# schematics.net
KiCad netlist of a schematic drawn in EAGLE
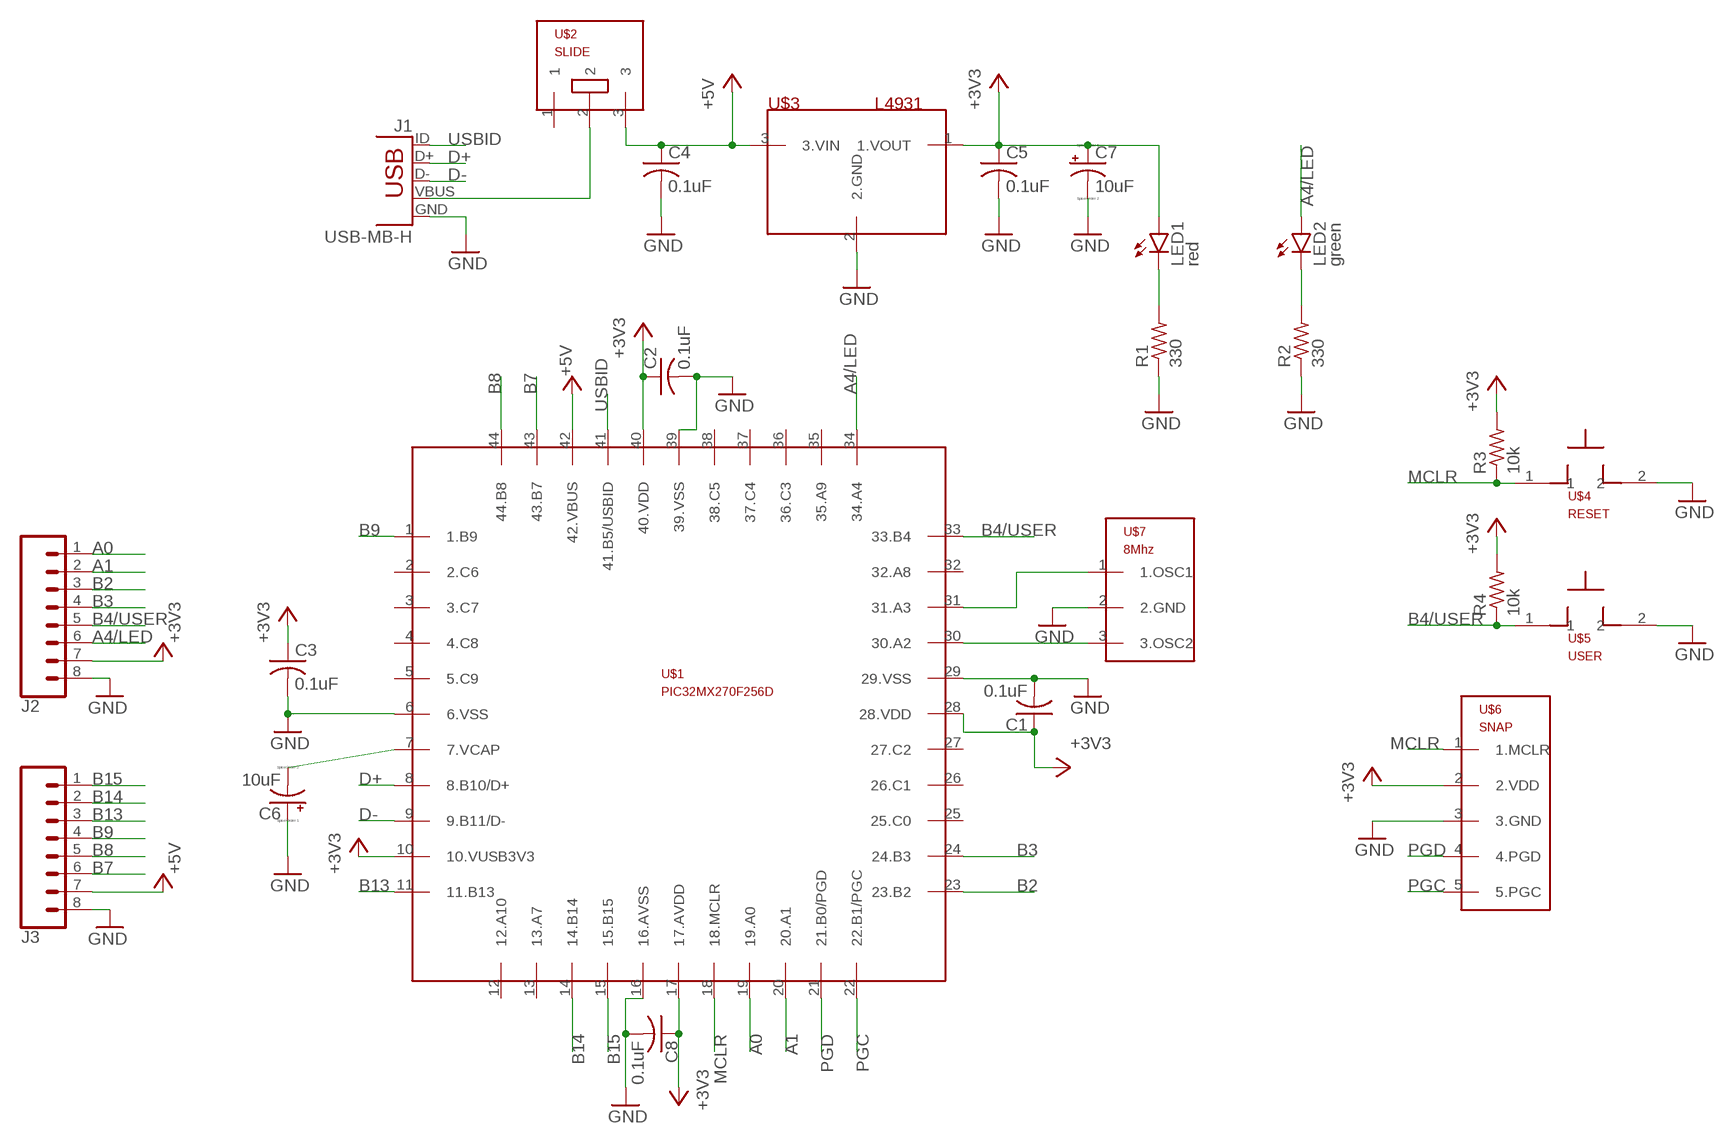
[diagram p0: schematic, sheet 1]

(export (version "E")
  (design (tool "Eeschema 10.0.6"))
  (components
    (comp (ref "C1")
      (value "0.1uF")
      (footprint "eagle-import:C025-025X050")
      (libsource (lib "eagle-import") (part "C-US025-025X050"))
    )
    (comp (ref "C2")
      (value "0.1uF")
      (footprint "eagle-import:C025-025X050")
      (libsource (lib "eagle-import") (part "C-US025-025X050"))
    )
    (comp (ref "C3")
      (value "0.1uF")
      (footprint "eagle-import:C025-025X050")
      (libsource (lib "eagle-import") (part "C-US025-025X050"))
    )
    (comp (ref "C4")
      (value "0.1uF")
      (footprint "eagle-import:C025-025X050")
      (libsource (lib "eagle-import") (part "C-US025-025X050"))
    )
    (comp (ref "C5")
      (value "0.1uF")
      (footprint "eagle-import:C025-025X050")
      (libsource (lib "eagle-import") (part "C-US025-025X050"))
    )
    (comp (ref "C6")
      (value "10uF")
      (footprint "eagle-import:B45181B")
      (libsource (lib "eagle-import") (part "CPOL-USB45181B"))
    )
    (comp (ref "C7")
      (value "10uF")
      (footprint "eagle-import:B45181B")
      (libsource (lib "eagle-import") (part "CPOL-USB45181B"))
    )
    (comp (ref "C8")
      (value "0.1uF")
      (footprint "eagle-import:C025-025X050")
      (libsource (lib "eagle-import") (part "C-US025-025X050"))
    )
    (comp (ref "J1")
      (value "USB-MB-H")
      (footprint "eagle-import:USB-MB-H")
      (libsource (lib "eagle-import") (part "USB-MB-H"))
    )
    (comp (ref "J2")
      (value "CONN_08\"")
      (footprint "eagle-import:1X08")
      (libsource (lib "eagle-import") (part "CONN_08{dblquote}"))
    )
    (comp (ref "J3")
      (value "CONN_08\"")
      (footprint "eagle-import:1X08")
      (libsource (lib "eagle-import") (part "CONN_08{dblquote}"))
    )
    (comp (ref "LED1")
      (value "red")
      (footprint "eagle-import:LED3MM")
      (libsource (lib "eagle-import") (part "LED3MM"))
    )
    (comp (ref "LED2")
      (value "green")
      (footprint "eagle-import:LED3MM")
      (libsource (lib "eagle-import") (part "LED3MM"))
    )
    (comp (ref "R1")
      (value "330")
      (footprint "eagle-import:0207_10")
      (libsource (lib "eagle-import") (part "R-US_0207/10"))
    )
    (comp (ref "R2")
      (value "330")
      (footprint "eagle-import:0207_10")
      (libsource (lib "eagle-import") (part "R-US_0207/10"))
    )
    (comp (ref "R3")
      (value "10k")
      (footprint "eagle-import:0207_10")
      (libsource (lib "eagle-import") (part "R-US_0207/10"))
    )
    (comp (ref "R4")
      (value "10k")
      (footprint "eagle-import:0207_10")
      (libsource (lib "eagle-import") (part "R-US_0207/10"))
    )
    (comp (ref "U$1")
      (value "PIC32MX270F256D")
      (footprint "eagle-import:TQFP44")
      (libsource (lib "eagle-import") (part "PIC32MX270F256D"))
    )
    (comp (ref "U$2")
      (value "SLIDE")
      (footprint "eagle-import:SLIDE")
      (libsource (lib "eagle-import") (part "SLIDE"))
    )
    (comp (ref "U$3")
      (value "L4931")
      (footprint "eagle-import:TO92")
      (libsource (lib "eagle-import") (part "L4931"))
    )
    (comp (ref "U$4")
      (value "RESET")
      (footprint "eagle-import:PB")
      (libsource (lib "eagle-import") (part "PB"))
    )
    (comp (ref "U$5")
      (value "USER")
      (footprint "eagle-import:PB")
      (libsource (lib "eagle-import") (part "PB"))
    )
    (comp (ref "U$6")
      (value "SNAP")
      (footprint "eagle-import:SNAP")
      (libsource (lib "eagle-import") (part "SNAP"))
    )
    (comp (ref "U$7")
      (value "8Mhz")
      (footprint "eagle-import:OSC")
      (libsource (lib "eagle-import") (part "OSC"))
    )
  )
  (nets
    (net (code "1") (name "+3V3") (class "Default")
      (node (ref "C1") (pin "1") (pinfunction "1_1") (pintype "passive"))
      (node (ref "C2") (pin "1") (pinfunction "1_1") (pintype "passive"))
      (node (ref "C3") (pin "1") (pinfunction "1_1") (pintype "passive"))
      (node (ref "C5") (pin "1") (pinfunction "1_1") (pintype "passive"))
      (node (ref "C7") (pin "+") (pinfunction "+_+") (pintype "passive"))
      (node (ref "C8") (pin "1") (pinfunction "1_1") (pintype "passive"))
      (node (ref "J2") (pin "7") (pinfunction "7_7") (pintype "passive"))
      (node (ref "LED1") (pin "A") (pinfunction "A_A") (pintype "passive"))
      (node (ref "R3") (pin "2") (pinfunction "2_2") (pintype "passive"))
      (node (ref "R4") (pin "2") (pinfunction "2_2") (pintype "passive"))
      (node (ref "U$1") (pin "10") (pinfunction "10.VUSB3V3_10") (pintype "bidirectional"))
      (node (ref "U$1") (pin "17") (pinfunction "17.AVDD_17") (pintype "bidirectional"))
      (node (ref "U$1") (pin "28") (pinfunction "28.VDD_28") (pintype "bidirectional"))
      (node (ref "U$1") (pin "40") (pinfunction "40.VDD_40") (pintype "bidirectional"))
      (node (ref "U$3") (pin "1") (pinfunction "1.VOUT_1") (pintype "bidirectional"))
      (node (ref "U$6") (pin "2") (pinfunction "2.VDD_2") (pintype "bidirectional"))
    )
    (net (code "2") (name "+5V") (class "Default")
      (node (ref "C4") (pin "1") (pinfunction "1_1") (pintype "passive"))
      (node (ref "J3") (pin "7") (pinfunction "7_7") (pintype "passive"))
      (node (ref "U$1") (pin "42") (pinfunction "42.VBUS_42") (pintype "bidirectional"))
      (node (ref "U$2") (pin "3") (pinfunction "3_3") (pintype "bidirectional"))
      (node (ref "U$3") (pin "3") (pinfunction "3.VIN_3") (pintype "bidirectional"))
    )
    (net (code "3") (name "/A0") (class "Default")
      (node (ref "J2") (pin "1") (pinfunction "1_1") (pintype "passive"))
      (node (ref "U$1") (pin "19") (pinfunction "19.A0_19") (pintype "bidirectional"))
    )
    (net (code "4") (name "/A1") (class "Default")
      (node (ref "J2") (pin "2") (pinfunction "2_2") (pintype "passive"))
      (node (ref "U$1") (pin "20") (pinfunction "20.A1_20") (pintype "bidirectional"))
    )
    (net (code "5") (name "/A4{slash}LED") (class "Default")
      (node (ref "J2") (pin "6") (pinfunction "6_6") (pintype "passive"))
      (node (ref "LED2") (pin "A") (pinfunction "A_A") (pintype "passive"))
      (node (ref "U$1") (pin "34") (pinfunction "34.A4_34") (pintype "bidirectional"))
    )
    (net (code "6") (name "/B2") (class "Default")
      (node (ref "J2") (pin "3") (pinfunction "3_3") (pintype "passive"))
      (node (ref "U$1") (pin "23") (pinfunction "23.B2_23") (pintype "bidirectional"))
    )
    (net (code "7") (name "/B3") (class "Default")
      (node (ref "J2") (pin "4") (pinfunction "4_4") (pintype "passive"))
      (node (ref "U$1") (pin "24") (pinfunction "24.B3_24") (pintype "bidirectional"))
    )
    (net (code "8") (name "/B4{slash}USER") (class "Default")
      (node (ref "J2") (pin "5") (pinfunction "5_5") (pintype "passive"))
      (node (ref "R4") (pin "1") (pinfunction "1_1") (pintype "passive"))
      (node (ref "U$1") (pin "33") (pinfunction "33.B4_33") (pintype "bidirectional"))
      (node (ref "U$5") (pin "1") (pinfunction "1_1") (pintype "bidirectional"))
    )
    (net (code "9") (name "/B7") (class "Default")
      (node (ref "J3") (pin "6") (pinfunction "6_6") (pintype "passive"))
      (node (ref "U$1") (pin "43") (pinfunction "43.B7_43") (pintype "bidirectional"))
    )
    (net (code "10") (name "/B8") (class "Default")
      (node (ref "J3") (pin "5") (pinfunction "5_5") (pintype "passive"))
      (node (ref "U$1") (pin "44") (pinfunction "44.B8_44") (pintype "bidirectional"))
    )
    (net (code "11") (name "/B9") (class "Default")
      (node (ref "J3") (pin "4") (pinfunction "4_4") (pintype "passive"))
      (node (ref "U$1") (pin "1") (pinfunction "1.B9_1") (pintype "bidirectional"))
    )
    (net (code "12") (name "/B13") (class "Default")
      (node (ref "J3") (pin "3") (pinfunction "3_3") (pintype "passive"))
      (node (ref "U$1") (pin "11") (pinfunction "11.B13_11") (pintype "bidirectional"))
    )
    (net (code "13") (name "/B14") (class "Default")
      (node (ref "J3") (pin "2") (pinfunction "2_2") (pintype "passive"))
      (node (ref "U$1") (pin "14") (pinfunction "14.B14_14") (pintype "bidirectional"))
    )
    (net (code "14") (name "/B15") (class "Default")
      (node (ref "J3") (pin "1") (pinfunction "1_1") (pintype "passive"))
      (node (ref "U$1") (pin "15") (pinfunction "15.B15_15") (pintype "bidirectional"))
    )
    (net (code "15") (name "/D+") (class "Default")
      (node (ref "J1") (pin "D+") (pinfunction "D+_D+") (pintype "bidirectional"))
      (node (ref "U$1") (pin "8") (pinfunction "8.B10/D+_8") (pintype "bidirectional"))
    )
    (net (code "16") (name "/D-") (class "Default")
      (node (ref "J1") (pin "D-") (pinfunction "D-_D-") (pintype "bidirectional"))
      (node (ref "U$1") (pin "9") (pinfunction "9.B11/D-_9") (pintype "bidirectional"))
    )
    (net (code "17") (name "/MCLR") (class "Default")
      (node (ref "R3") (pin "1") (pinfunction "1_1") (pintype "passive"))
      (node (ref "U$1") (pin "18") (pinfunction "18.MCLR_18") (pintype "bidirectional"))
      (node (ref "U$4") (pin "1") (pinfunction "1_1") (pintype "bidirectional"))
      (node (ref "U$6") (pin "1") (pinfunction "1.MCLR_1") (pintype "bidirectional"))
    )
    (net (code "18") (name "/PGC") (class "Default")
      (node (ref "U$1") (pin "22") (pinfunction "22.B1/PGC_22") (pintype "bidirectional"))
      (node (ref "U$6") (pin "5") (pinfunction "5.PGC_5") (pintype "bidirectional"))
    )
    (net (code "19") (name "/PGD") (class "Default")
      (node (ref "U$1") (pin "21") (pinfunction "21.B0/PGD_21") (pintype "bidirectional"))
      (node (ref "U$6") (pin "4") (pinfunction "4.PGD_4") (pintype "bidirectional"))
    )
    (net (code "20") (name "/USBID") (class "Default")
      (node (ref "J1") (pin "ID") (pinfunction "ID_ID") (pintype "bidirectional"))
      (node (ref "U$1") (pin "41") (pinfunction "41.B5/USBID_41") (pintype "bidirectional"))
    )
    (net (code "21") (name "GND") (class "Default")
      (node (ref "C1") (pin "2") (pinfunction "2_2") (pintype "passive"))
      (node (ref "C2") (pin "2") (pinfunction "2_2") (pintype "passive"))
      (node (ref "C3") (pin "2") (pinfunction "2_2") (pintype "passive"))
      (node (ref "C4") (pin "2") (pinfunction "2_2") (pintype "passive"))
      (node (ref "C5") (pin "2") (pinfunction "2_2") (pintype "passive"))
      (node (ref "C6") (pin "+") (pinfunction "+_+") (pintype "passive"))
      (node (ref "C7") (pin "-") (pinfunction "-_-") (pintype "passive"))
      (node (ref "C8") (pin "2") (pinfunction "2_2") (pintype "passive"))
      (node (ref "J1") (pin "GND") (pinfunction "GND_GND") (pintype "bidirectional"))
      (node (ref "J2") (pin "8") (pinfunction "8_8") (pintype "passive"))
      (node (ref "J3") (pin "8") (pinfunction "8_8") (pintype "passive"))
      (node (ref "R1") (pin "1") (pinfunction "1_1") (pintype "passive"))
      (node (ref "R2") (pin "1") (pinfunction "1_1") (pintype "passive"))
      (node (ref "U$1") (pin "16") (pinfunction "16.AVSS_16") (pintype "bidirectional"))
      (node (ref "U$1") (pin "29") (pinfunction "29.VSS_29") (pintype "bidirectional"))
      (node (ref "U$1") (pin "39") (pinfunction "39.VSS_39") (pintype "bidirectional"))
      (node (ref "U$1") (pin "6") (pinfunction "6.VSS_6") (pintype "bidirectional"))
      (node (ref "U$3") (pin "2") (pinfunction "2.GND_2") (pintype "bidirectional"))
      (node (ref "U$4") (pin "2") (pinfunction "2_2") (pintype "bidirectional"))
      (node (ref "U$5") (pin "2") (pinfunction "2_2") (pintype "bidirectional"))
      (node (ref "U$6") (pin "3") (pinfunction "3.GND_3") (pintype "bidirectional"))
      (node (ref "U$7") (pin "2") (pinfunction "2.GND_2") (pintype "bidirectional"))
    )
    (net (code "22") (name "Net-(J1-PadVBUS)") (class "Default")
      (node (ref "J1") (pin "VBUS") (pinfunction "VBUS_VBUS") (pintype "bidirectional"))
      (node (ref "U$2") (pin "2") (pinfunction "2_2") (pintype "bidirectional"))
    )
    (net (code "23") (name "Net-(LED1-C)") (class "Default")
      (node (ref "LED1") (pin "K") (pinfunction "C_K") (pintype "passive"))
      (node (ref "R1") (pin "2") (pinfunction "2_2") (pintype "passive"))
    )
    (net (code "24") (name "Net-(LED2-C)") (class "Default")
      (node (ref "LED2") (pin "K") (pinfunction "C_K") (pintype "passive"))
      (node (ref "R2") (pin "2") (pinfunction "2_2") (pintype "passive"))
    )
    (net (code "25") (name "Net-(U$1-7.VCAP)") (class "Default")
      (node (ref "C6") (pin "-") (pinfunction "-_-") (pintype "passive"))
      (node (ref "U$1") (pin "7") (pinfunction "7.VCAP_7") (pintype "bidirectional"))
    )
    (net (code "26") (name "Net-(U$1-30.A2)") (class "Default")
      (node (ref "U$1") (pin "30") (pinfunction "30.A2_30") (pintype "bidirectional"))
      (node (ref "U$7") (pin "3") (pinfunction "3.OSC2_3") (pintype "bidirectional"))
    )
    (net (code "27") (name "Net-(U$1-31.A3)") (class "Default")
      (node (ref "U$1") (pin "31") (pinfunction "31.A3_31") (pintype "bidirectional"))
      (node (ref "U$7") (pin "1") (pinfunction "1.OSC1_1") (pintype "bidirectional"))
    )
    (net (code "28") (name "unconnected-(U$1-2.C6-Pad2)") (class "Default")
      (node (ref "U$1") (pin "2") (pinfunction "2.C6_2") (pintype "bidirectional"))
    )
    (net (code "29") (name "unconnected-(U$1-3.C7-Pad3)") (class "Default")
      (node (ref "U$1") (pin "3") (pinfunction "3.C7_3") (pintype "bidirectional"))
    )
    (net (code "30") (name "unconnected-(U$1-4.C8-Pad4)") (class "Default")
      (node (ref "U$1") (pin "4") (pinfunction "4.C8_4") (pintype "bidirectional"))
    )
    (net (code "31") (name "unconnected-(U$1-5.C9-Pad5)") (class "Default")
      (node (ref "U$1") (pin "5") (pinfunction "5.C9_5") (pintype "bidirectional"))
    )
    (net (code "32") (name "unconnected-(U$1-12.A10-Pad12)") (class "Default")
      (node (ref "U$1") (pin "12") (pinfunction "12.A10_12") (pintype "bidirectional"))
    )
    (net (code "33") (name "unconnected-(U$1-13.A7-Pad13)") (class "Default")
      (node (ref "U$1") (pin "13") (pinfunction "13.A7_13") (pintype "bidirectional"))
    )
    (net (code "34") (name "unconnected-(U$1-25.C0-Pad25)") (class "Default")
      (node (ref "U$1") (pin "25") (pinfunction "25.C0_25") (pintype "bidirectional"))
    )
    (net (code "35") (name "unconnected-(U$1-26.C1-Pad26)") (class "Default")
      (node (ref "U$1") (pin "26") (pinfunction "26.C1_26") (pintype "bidirectional"))
    )
    (net (code "36") (name "unconnected-(U$1-27.C2-Pad27)") (class "Default")
      (node (ref "U$1") (pin "27") (pinfunction "27.C2_27") (pintype "bidirectional"))
    )
    (net (code "37") (name "unconnected-(U$1-32.A8-Pad32)") (class "Default")
      (node (ref "U$1") (pin "32") (pinfunction "32.A8_32") (pintype "bidirectional"))
    )
    (net (code "38") (name "unconnected-(U$1-35.A9-Pad35)") (class "Default")
      (node (ref "U$1") (pin "35") (pinfunction "35.A9_35") (pintype "bidirectional"))
    )
    (net (code "39") (name "unconnected-(U$1-36.C3-Pad36)") (class "Default")
      (node (ref "U$1") (pin "36") (pinfunction "36.C3_36") (pintype "bidirectional"))
    )
    (net (code "40") (name "unconnected-(U$1-37.C4-Pad37)") (class "Default")
      (node (ref "U$1") (pin "37") (pinfunction "37.C4_37") (pintype "bidirectional"))
    )
    (net (code "41") (name "unconnected-(U$1-38.C5-Pad38)") (class "Default")
      (node (ref "U$1") (pin "38") (pinfunction "38.C5_38") (pintype "bidirectional"))
    )
    (net (code "42") (name "unconnected-(U$2-Pad1)") (class "Default")
      (node (ref "U$2") (pin "1") (pinfunction "1_1") (pintype "bidirectional"))
    )
  )
)
